# badge_spacehuhn.net
KiCad netlist of a schematic drawn in EAGLE
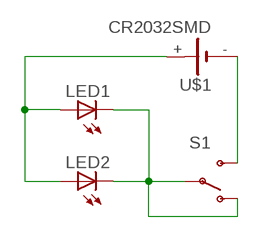
[diagram p0: schematic, sheet 1]

(export (version "E")
  (design (tool "Eeschema 10.0.6"))
  (components
    (comp (ref "LED1")
      (value "LED5MM")
      (footprint "eagle-import:LED5MM")
      (libsource (lib "eagle-import") (part "LED5MM"))
    )
    (comp (ref "LED2")
      (value "LED5MM")
      (footprint "eagle-import:LED5MM")
      (libsource (lib "eagle-import") (part "LED5MM"))
    )
    (comp (ref "S1")
      (value "SWITCH-SPDT-SMD-A")
      (footprint "eagle-import:SWITCH-SPST-SMD-A")
      (libsource (lib "eagle-import") (part "SWITCH-SPDT-SMD-A"))
    )
    (comp (ref "U$1")
      (value "CR2032SMD")
      (footprint "eagle-import:CR2032SMD")
      (libsource (lib "eagle-import") (part "CR2032SMD"))
    )
  )
  (nets
    (net (code "1") (name "Net-(LED1-C)") (class "Default")
      (node (ref "LED1") (pin "K") (pinfunction "C_K") (pintype "passive"))
      (node (ref "LED2") (pin "K") (pinfunction "C_K") (pintype "passive"))
      (node (ref "S1") (pin "1") (pinfunction "O_1") (pintype "passive"))
      (node (ref "S1") (pin "2") (pinfunction "P_2") (pintype "passive"))
    )
    (net (code "2") (name "Net-(LED1-PadA)") (class "Default")
      (node (ref "LED1") (pin "A") (pinfunction "A_A") (pintype "passive"))
      (node (ref "LED2") (pin "A") (pinfunction "A_A") (pintype "passive"))
      (node (ref "U$1") (pin "+") (pinfunction "+_+") (pintype "passive"))
    )
    (net (code "3") (name "Net-(S1-S)") (class "Default")
      (node (ref "S1") (pin "3") (pinfunction "S_3") (pintype "passive"))
      (node (ref "U$1") (pin "-") (pinfunction "-_-") (pintype "passive"))
    )
  )
)
